# tfg.net
KiCad netlist of a schematic drawn in EAGLE
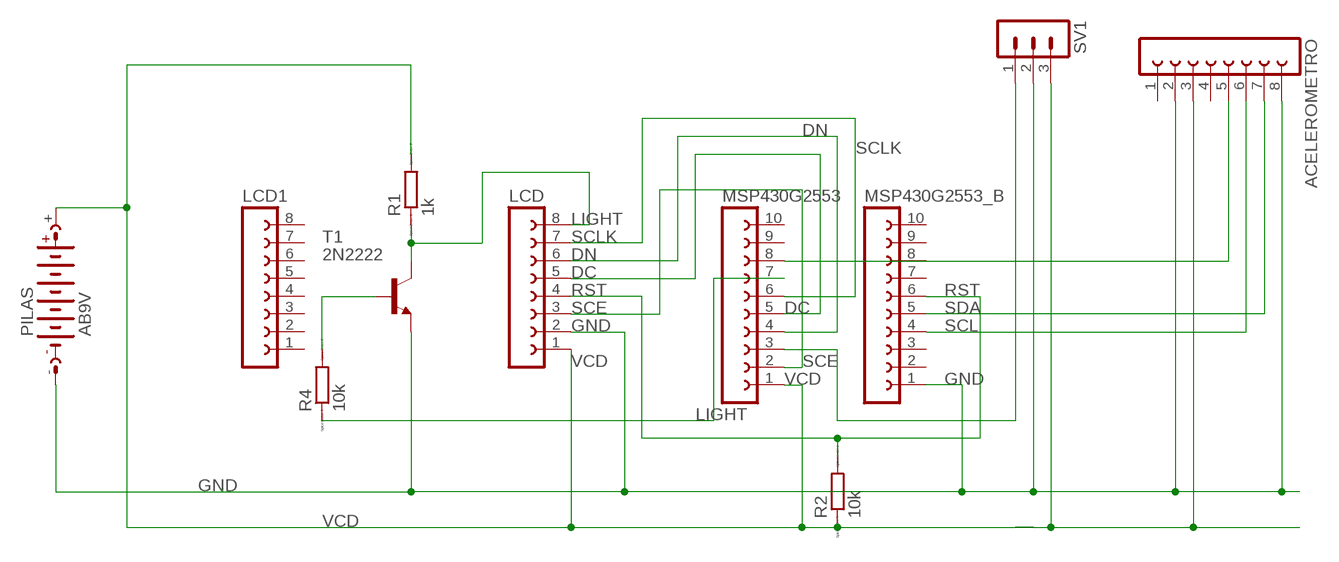
[diagram p0: schematic, sheet 1]

(export (version "E")
  (design (tool "Eeschema 10.0.6"))
  (components
    (comp (ref "ACELEROMETRO")
      (value "FE08-1")
      (footprint "eagle-import:FE08")
      (libsource (lib "eagle-import") (part "FE08-1"))
    )
    (comp (ref "LCD")
      (value "FE08-1")
      (footprint "eagle-import:FE08")
      (libsource (lib "eagle-import") (part "FE08-1"))
    )
    (comp (ref "LCD1")
      (value "FE08-1")
      (footprint "eagle-import:FE08")
      (libsource (lib "eagle-import") (part "FE08-1"))
    )
    (comp (ref "MSP430G2553")
      (value "FE10-1")
      (footprint "eagle-import:FE10")
      (libsource (lib "eagle-import") (part "FE10-1"))
    )
    (comp (ref "MSP430G2553_B")
      (value "FE10-1")
      (footprint "eagle-import:FE10")
      (libsource (lib "eagle-import") (part "FE10-1"))
    )
    (comp (ref "PILAS")
      (value "AB9V")
      (footprint "eagle-import:AB9V")
      (libsource (lib "eagle-import") (part "AB9V"))
    )
    (comp (ref "R1")
      (value "1k")
      (footprint "eagle-import:0207_10")
      (libsource (lib "eagle-import") (part "R0207/10"))
    )
    (comp (ref "R2")
      (value "10k")
      (footprint "eagle-import:0207_10")
      (libsource (lib "eagle-import") (part "R0207/10"))
    )
    (comp (ref "R4")
      (value "10k")
      (footprint "eagle-import:0207_10")
      (libsource (lib "eagle-import") (part "R0207/10"))
    )
    (comp (ref "SV1")
      (value "MA03-1")
      (footprint "eagle-import:MA03-1")
      (libsource (lib "eagle-import") (part "MA03-1"))
    )
    (comp (ref "T1")
      (value "2N2222")
      (footprint "eagle-import:TO18")
      (fields (field (name "SPICEPREFIX") "J"))
      (libsource (lib "eagle-import") (part "2N2222"))
    )
  )
  (nets
    (net (code "1") (name "/DC") (class "Default")
      (node (ref "LCD") (pin "5") (pinfunction "5_5") (pintype "passive"))
      (node (ref "MSP430G2553") (pin "5") (pinfunction "5_5") (pintype "passive"))
    )
    (net (code "2") (name "/DN") (class "Default")
      (node (ref "LCD") (pin "6") (pinfunction "6_6") (pintype "passive"))
      (node (ref "MSP430G2553") (pin "4") (pinfunction "4_4") (pintype "passive"))
    )
    (net (code "3") (name "/GND") (class "Default")
      (node (ref "ACELEROMETRO") (pin "2") (pinfunction "2_2") (pintype "passive"))
      (node (ref "ACELEROMETRO") (pin "8") (pinfunction "8_8") (pintype "passive"))
      (node (ref "LCD") (pin "2") (pinfunction "2_2") (pintype "passive"))
      (node (ref "MSP430G2553_B") (pin "1") (pinfunction "1_1") (pintype "passive"))
      (node (ref "PILAS") (pin "-") (pinfunction "-_-") (pintype "passive"))
      (node (ref "SV1") (pin "2") (pinfunction "2_2") (pintype "passive"))
      (node (ref "T1") (pin "1") (pinfunction "E_1") (pintype "passive"))
    )
    (net (code "4") (name "/LIGHT") (class "Default")
      (node (ref "MSP430G2553") (pin "7") (pinfunction "7_7") (pintype "passive"))
      (node (ref "R4") (pin "1") (pinfunction "1_1") (pintype "passive"))
    )
    (net (code "5") (name "/RST") (class "Default")
      (node (ref "LCD") (pin "4") (pinfunction "4_4") (pintype "passive"))
      (node (ref "MSP430G2553_B") (pin "6") (pinfunction "6_6") (pintype "passive"))
      (node (ref "R2") (pin "2") (pinfunction "2_2") (pintype "passive"))
    )
    (net (code "6") (name "/SCE") (class "Default")
      (node (ref "LCD") (pin "3") (pinfunction "3_3") (pintype "passive"))
      (node (ref "MSP430G2553") (pin "2") (pinfunction "2_2") (pintype "passive"))
    )
    (net (code "7") (name "/SCL") (class "Default")
      (node (ref "ACELEROMETRO") (pin "6") (pinfunction "6_6") (pintype "passive"))
      (node (ref "MSP430G2553_B") (pin "4") (pinfunction "4_4") (pintype "passive"))
    )
    (net (code "8") (name "/SCLK") (class "Default")
      (node (ref "LCD") (pin "7") (pinfunction "7_7") (pintype "passive"))
      (node (ref "MSP430G2553") (pin "6") (pinfunction "6_6") (pintype "passive"))
    )
    (net (code "9") (name "/SDA") (class "Default")
      (node (ref "ACELEROMETRO") (pin "7") (pinfunction "7_7") (pintype "passive"))
      (node (ref "MSP430G2553_B") (pin "5") (pinfunction "5_5") (pintype "passive"))
    )
    (net (code "10") (name "/VCD") (class "Default")
      (node (ref "ACELEROMETRO") (pin "3") (pinfunction "3_3") (pintype "passive"))
      (node (ref "LCD") (pin "1") (pinfunction "1_1") (pintype "passive"))
      (node (ref "MSP430G2553") (pin "1") (pinfunction "1_1") (pintype "passive"))
      (node (ref "PILAS") (pin "+") (pinfunction "+_+") (pintype "passive"))
      (node (ref "R1") (pin "2") (pinfunction "2_2") (pintype "passive"))
      (node (ref "R2") (pin "1") (pinfunction "1_1") (pintype "passive"))
      (node (ref "SV1") (pin "3") (pinfunction "3_3") (pintype "passive"))
    )
    (net (code "11") (name "Net-(ACELEROMETRO-Pad5)") (class "Default")
      (node (ref "ACELEROMETRO") (pin "5") (pinfunction "5_5") (pintype "passive"))
      (node (ref "MSP430G2553") (pin "8") (pinfunction "8_8") (pintype "passive"))
    )
    (net (code "12") (name "Net-(MSP430G2553-Pad3)") (class "Default")
      (node (ref "MSP430G2553") (pin "3") (pinfunction "3_3") (pintype "passive"))
      (node (ref "SV1") (pin "1") (pinfunction "1_1") (pintype "passive"))
    )
    (net (code "13") (name "Net-(T1-B)") (class "Default")
      (node (ref "R4") (pin "2") (pinfunction "2_2") (pintype "passive"))
      (node (ref "T1") (pin "2") (pinfunction "B_2") (pintype "passive"))
    )
    (net (code "14") (name "Net-(T1-C)") (class "Default")
      (node (ref "LCD") (pin "8") (pinfunction "8_8") (pintype "passive"))
      (node (ref "R1") (pin "1") (pinfunction "1_1") (pintype "passive"))
      (node (ref "T1") (pin "3") (pinfunction "C_3") (pintype "passive"))
    )
    (net (code "15") (name "unconnected-(ACELEROMETRO-Pad1)") (class "Default")
      (node (ref "ACELEROMETRO") (pin "1") (pinfunction "1_1") (pintype "passive"))
    )
    (net (code "16") (name "unconnected-(ACELEROMETRO-Pad4)") (class "Default")
      (node (ref "ACELEROMETRO") (pin "4") (pinfunction "4_4") (pintype "passive"))
    )
    (net (code "17") (name "unconnected-(LCD1-Pad1)") (class "Default")
      (node (ref "LCD1") (pin "1") (pinfunction "1_1") (pintype "passive"))
    )
    (net (code "18") (name "unconnected-(LCD1-Pad2)") (class "Default")
      (node (ref "LCD1") (pin "2") (pinfunction "2_2") (pintype "passive"))
    )
    (net (code "19") (name "unconnected-(LCD1-Pad3)") (class "Default")
      (node (ref "LCD1") (pin "3") (pinfunction "3_3") (pintype "passive"))
    )
    (net (code "20") (name "unconnected-(LCD1-Pad4)") (class "Default")
      (node (ref "LCD1") (pin "4") (pinfunction "4_4") (pintype "passive"))
    )
    (net (code "21") (name "unconnected-(LCD1-Pad5)") (class "Default")
      (node (ref "LCD1") (pin "5") (pinfunction "5_5") (pintype "passive"))
    )
    (net (code "22") (name "unconnected-(LCD1-Pad6)") (class "Default")
      (node (ref "LCD1") (pin "6") (pinfunction "6_6") (pintype "passive"))
    )
    (net (code "23") (name "unconnected-(LCD1-Pad7)") (class "Default")
      (node (ref "LCD1") (pin "7") (pinfunction "7_7") (pintype "passive"))
    )
    (net (code "24") (name "unconnected-(LCD1-Pad8)") (class "Default")
      (node (ref "LCD1") (pin "8") (pinfunction "8_8") (pintype "passive"))
    )
    (net (code "25") (name "unconnected-(MSP430G2553-Pad9)") (class "Default")
      (node (ref "MSP430G2553") (pin "9") (pinfunction "9_9") (pintype "passive"))
    )
    (net (code "26") (name "unconnected-(MSP430G2553-Pad10)") (class "Default")
      (node (ref "MSP430G2553") (pin "10") (pinfunction "10_10") (pintype "passive"))
    )
    (net (code "27") (name "unconnected-(MSP430G2553_B-Pad2)") (class "Default")
      (node (ref "MSP430G2553_B") (pin "2") (pinfunction "2_2") (pintype "passive"))
    )
    (net (code "28") (name "unconnected-(MSP430G2553_B-Pad3)") (class "Default")
      (node (ref "MSP430G2553_B") (pin "3") (pinfunction "3_3") (pintype "passive"))
    )
    (net (code "29") (name "unconnected-(MSP430G2553_B-Pad7)") (class "Default")
      (node (ref "MSP430G2553_B") (pin "7") (pinfunction "7_7") (pintype "passive"))
    )
    (net (code "30") (name "unconnected-(MSP430G2553_B-Pad8)") (class "Default")
      (node (ref "MSP430G2553_B") (pin "8") (pinfunction "8_8") (pintype "passive"))
    )
    (net (code "31") (name "unconnected-(MSP430G2553_B-Pad9)") (class "Default")
      (node (ref "MSP430G2553_B") (pin "9") (pinfunction "9_9") (pintype "passive"))
    )
    (net (code "32") (name "unconnected-(MSP430G2553_B-Pad10)") (class "Default")
      (node (ref "MSP430G2553_B") (pin "10") (pinfunction "10_10") (pintype "passive"))
    )
  )
)
